# USBHume2.net
KiCad netlist of a schematic drawn in EAGLE
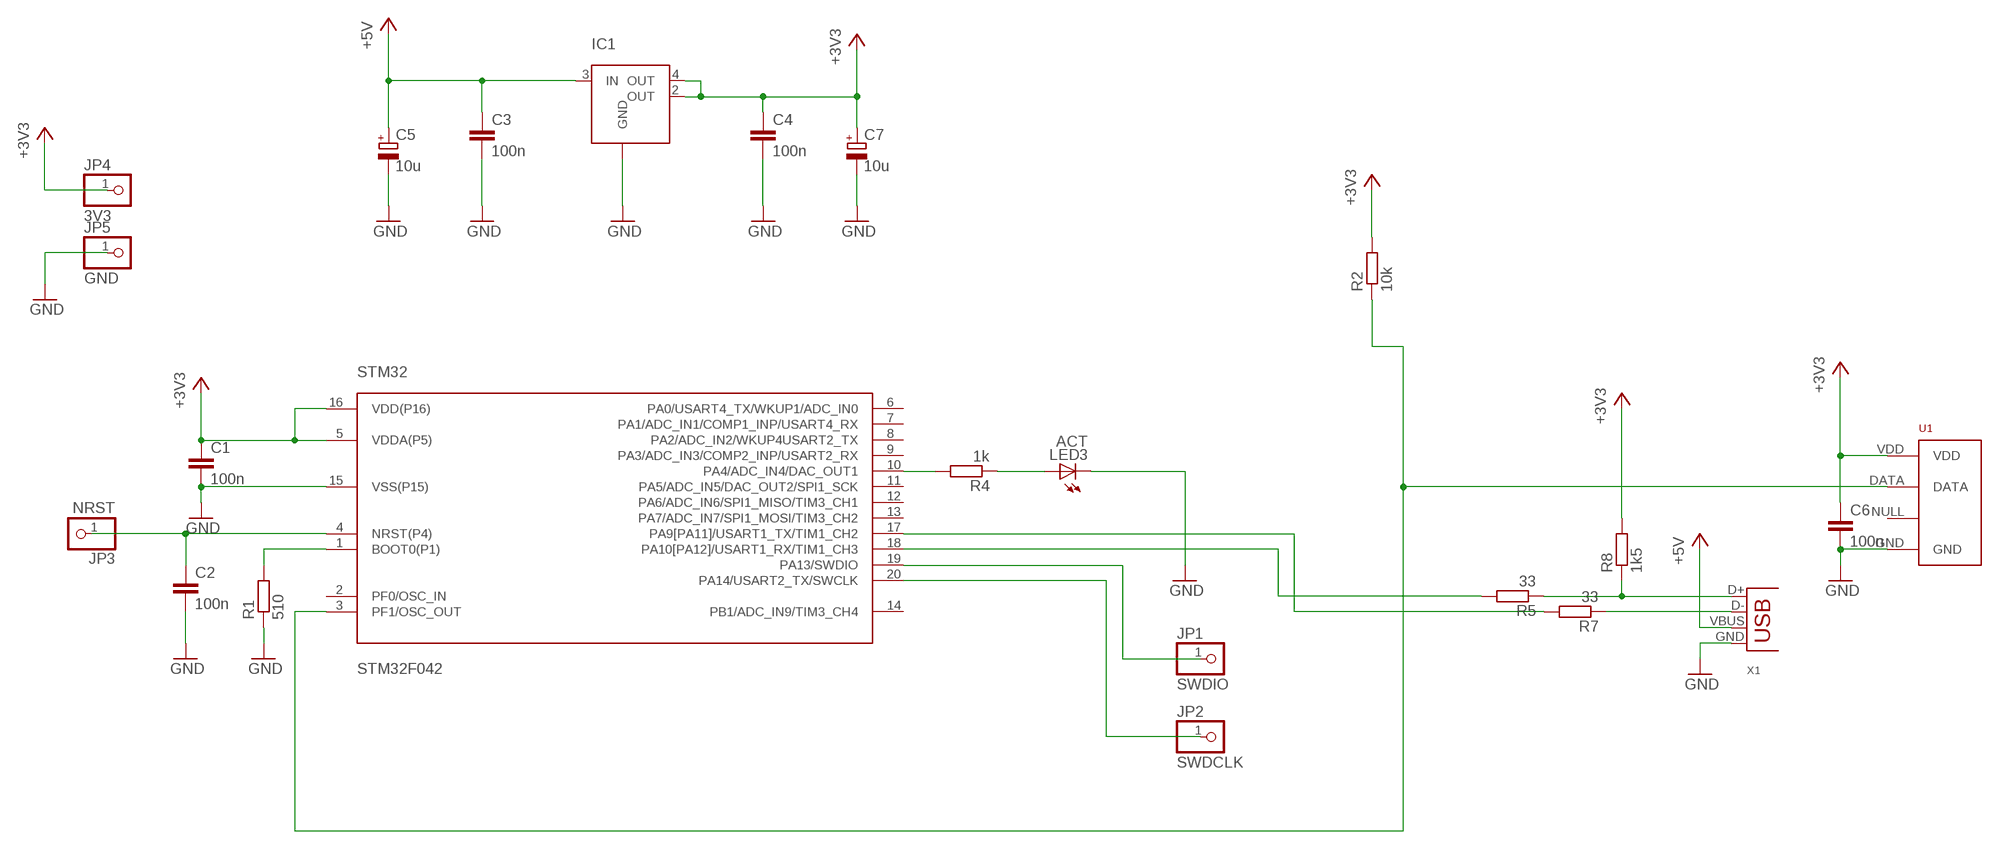
[diagram p0: schematic, sheet 1]

(export (version "E")
  (design (tool "Eeschema 10.0.6"))
  (components
    (comp (ref "C1")
      (value "100n")
      (footprint "eagle-import:C0805")
      (libsource (lib "eagle-import") (part "C-EUC0805"))
    )
    (comp (ref "C2")
      (value "100n")
      (footprint "eagle-import:C0805")
      (libsource (lib "eagle-import") (part "C-EUC0805"))
    )
    (comp (ref "C3")
      (value "100n")
      (footprint "eagle-import:C0805")
      (libsource (lib "eagle-import") (part "C-EUC0805"))
    )
    (comp (ref "C4")
      (value "100n")
      (footprint "eagle-import:C0805")
      (libsource (lib "eagle-import") (part "C-EUC0805"))
    )
    (comp (ref "C5")
      (value "10u")
      (footprint "eagle-import:A_3216-18W")
      (libsource (lib "eagle-import") (part "CPOL-EUA/3216-18W"))
    )
    (comp (ref "C6")
      (value "100n")
      (footprint "eagle-import:C0805")
      (libsource (lib "eagle-import") (part "C-EUC0805"))
    )
    (comp (ref "C7")
      (value "10u")
      (footprint "eagle-import:A_3216-18W")
      (libsource (lib "eagle-import") (part "CPOL-EUA/3216-18W"))
    )
    (comp (ref "IC1")
      (value "LM1117MP-3.3")
      (footprint "eagle-import:SOT223")
      (libsource (lib "eagle-import") (part "LM1117MP-3.3"))
    )
    (comp (ref "JP1")
      (value "SWDIO")
      (footprint "eagle-import:1X01")
      (libsource (lib "eagle-import") (part "PINHD-1X1"))
    )
    (comp (ref "JP2")
      (value "SWDCLK")
      (footprint "eagle-import:1X01")
      (libsource (lib "eagle-import") (part "PINHD-1X1"))
    )
    (comp (ref "JP3")
      (value "NRST")
      (footprint "eagle-import:1X01")
      (libsource (lib "eagle-import") (part "PINHD-1X1"))
    )
    (comp (ref "JP4")
      (value "3V3")
      (footprint "eagle-import:1X01")
      (libsource (lib "eagle-import") (part "PINHD-1X1"))
    )
    (comp (ref "JP5")
      (value "GND")
      (footprint "eagle-import:1X01")
      (libsource (lib "eagle-import") (part "PINHD-1X1"))
    )
    (comp (ref "LED3")
      (value "ACT")
      (footprint "eagle-import:CHIPLED_0805")
      (libsource (lib "eagle-import") (part "LEDCHIPLED_0805"))
    )
    (comp (ref "R1")
      (value "510")
      (footprint "eagle-import:M0805")
      (libsource (lib "eagle-import") (part "R-EU_M0805"))
    )
    (comp (ref "R2")
      (value "10k")
      (footprint "eagle-import:M0805")
      (libsource (lib "eagle-import") (part "R-EU_M0805"))
    )
    (comp (ref "R4")
      (value "1k")
      (footprint "eagle-import:M0805")
      (libsource (lib "eagle-import") (part "R-EU_M0805"))
    )
    (comp (ref "R5")
      (value "33")
      (footprint "eagle-import:M0805")
      (libsource (lib "eagle-import") (part "R-EU_M0805"))
    )
    (comp (ref "R7")
      (value "33")
      (footprint "eagle-import:M0805")
      (libsource (lib "eagle-import") (part "R-EU_M0805"))
    )
    (comp (ref "R8")
      (value "1k5")
      (footprint "eagle-import:M0805")
      (libsource (lib "eagle-import") (part "R-EU_M0805"))
    )
    (comp (ref "STM32")
      (value "STM32F042")
      (footprint "eagle-import:TSSOP20")
      (libsource (lib "eagle-import") (part "STM32F042"))
    )
    (comp (ref "U1")
      (value "RHT03_DHT-22_AM2302WIRED")
      (footprint "eagle-import:AM2302")
      (libsource (lib "eagle-import") (part "RHT03_DHT-22_AM2302WIRED"))
    )
    (comp (ref "X1")
      (value "USB-A-H")
      (footprint "eagle-import:USB-A-H")
      (libsource (lib "eagle-import") (part "USB-A-H"))
    )
  )
  (nets
    (net (code "1") (name "+3V3") (class "Default")
      (node (ref "C1") (pin "1") (pinfunction "1_1") (pintype "passive"))
      (node (ref "C4") (pin "1") (pinfunction "1_1") (pintype "passive"))
      (node (ref "C6") (pin "1") (pinfunction "1_1") (pintype "passive"))
      (node (ref "C7") (pin "+") (pinfunction "+_+") (pintype "passive"))
      (node (ref "IC1") (pin "2") (pinfunction "OUT_2") (pintype "power_in"))
      (node (ref "IC1") (pin "4") (pinfunction "OUT_4") (pintype "power_in"))
      (node (ref "JP4") (pin "1") (pinfunction "1_1") (pintype "passive"))
      (node (ref "R2") (pin "2") (pinfunction "2_2") (pintype "passive"))
      (node (ref "R8") (pin "2") (pinfunction "2_2") (pintype "passive"))
      (node (ref "STM32") (pin "16") (pinfunction "VDD(P16)_16") (pintype "bidirectional"))
      (node (ref "STM32") (pin "5") (pinfunction "VDDA(P5)_5") (pintype "bidirectional"))
      (node (ref "U1") (pin "VDD") (pinfunction "VDD_VDD") (pintype "power_in"))
    )
    (net (code "2") (name "+5V") (class "Default")
      (node (ref "C3") (pin "1") (pinfunction "1_1") (pintype "passive"))
      (node (ref "C5") (pin "+") (pinfunction "+_+") (pintype "passive"))
      (node (ref "IC1") (pin "3") (pinfunction "IN_3") (pintype "power_in"))
      (node (ref "X1") (pin "VBUS") (pinfunction "VBUS_VBUS") (pintype "bidirectional"))
    )
    (net (code "3") (name "GND") (class "Default")
      (node (ref "C1") (pin "2") (pinfunction "2_2") (pintype "passive"))
      (node (ref "C2") (pin "2") (pinfunction "2_2") (pintype "passive"))
      (node (ref "C3") (pin "2") (pinfunction "2_2") (pintype "passive"))
      (node (ref "C4") (pin "2") (pinfunction "2_2") (pintype "passive"))
      (node (ref "C5") (pin "-") (pinfunction "-_-") (pintype "passive"))
      (node (ref "C6") (pin "2") (pinfunction "2_2") (pintype "passive"))
      (node (ref "C7") (pin "-") (pinfunction "-_-") (pintype "passive"))
      (node (ref "IC1") (pin "1") (pinfunction "GND_1") (pintype "power_in"))
      (node (ref "JP5") (pin "1") (pinfunction "1_1") (pintype "passive"))
      (node (ref "LED3") (pin "C") (pinfunction "C_C") (pintype "passive"))
      (node (ref "R1") (pin "1") (pinfunction "1_1") (pintype "passive"))
      (node (ref "STM32") (pin "15") (pinfunction "VSS(P15)_15") (pintype "bidirectional"))
      (node (ref "U1") (pin "GND") (pinfunction "GND_GND") (pintype "power_in"))
      (node (ref "X1") (pin "GND") (pinfunction "GND_GND") (pintype "bidirectional"))
    )
    (net (code "4") (name "Net-(LED3-PadA)") (class "Default")
      (node (ref "LED3") (pin "A") (pinfunction "A_A") (pintype "passive"))
      (node (ref "R4") (pin "1") (pinfunction "1_1") (pintype "passive"))
    )
    (net (code "5") (name "Net-(R5-Pad1)") (class "Default")
      (node (ref "R5") (pin "1") (pinfunction "1_1") (pintype "passive"))
      (node (ref "R8") (pin "1") (pinfunction "1_1") (pintype "passive"))
      (node (ref "X1") (pin "D+") (pinfunction "D+_D+") (pintype "bidirectional"))
    )
    (net (code "6") (name "Net-(R7-Pad1)") (class "Default")
      (node (ref "R7") (pin "1") (pinfunction "1_1") (pintype "passive"))
      (node (ref "X1") (pin "D-") (pinfunction "D-_D-") (pintype "bidirectional"))
    )
    (net (code "7") (name "Net-(STM32-BOOT0(P1))") (class "Default")
      (node (ref "R1") (pin "2") (pinfunction "2_2") (pintype "passive"))
      (node (ref "STM32") (pin "1") (pinfunction "BOOT0(P1)_1") (pintype "bidirectional"))
    )
    (net (code "8") (name "Net-(STM32-NRST(P4))") (class "Default")
      (node (ref "C2") (pin "1") (pinfunction "1_1") (pintype "passive"))
      (node (ref "JP3") (pin "1") (pinfunction "1_1") (pintype "passive"))
      (node (ref "STM32") (pin "4") (pinfunction "NRST(P4)_4") (pintype "bidirectional"))
    )
    (net (code "9") (name "Net-(STM32-PA4{slash}ADC_IN4{slash}DAC_OUT1)") (class "Default")
      (node (ref "R4") (pin "2") (pinfunction "2_2") (pintype "passive"))
      (node (ref "STM32") (pin "10") (pinfunction "PA4/ADC_IN4/DAC_OUT1_10") (pintype "bidirectional"))
    )
    (net (code "10") (name "Net-(STM32-PA9[PA11]{slash}USART1_TX{slash}TIM1_CH2)") (class "Default")
      (node (ref "R7") (pin "2") (pinfunction "2_2") (pintype "passive"))
      (node (ref "STM32") (pin "17") (pinfunction "PA9[PA11]/USART1_TX/TIM1_CH2_17") (pintype "bidirectional"))
    )
    (net (code "11") (name "Net-(STM32-PA10[PA12]{slash}USART1_RX{slash}TIM1_CH3)") (class "Default")
      (node (ref "R5") (pin "2") (pinfunction "2_2") (pintype "passive"))
      (node (ref "STM32") (pin "18") (pinfunction "PA10[PA12]/USART1_RX/TIM1_CH3_18") (pintype "bidirectional"))
    )
    (net (code "12") (name "Net-(STM32-PA13{slash}SWDIO)") (class "Default")
      (node (ref "JP1") (pin "1") (pinfunction "1_1") (pintype "passive"))
      (node (ref "STM32") (pin "19") (pinfunction "PA13/SWDIO_19") (pintype "bidirectional"))
    )
    (net (code "13") (name "Net-(STM32-PA14{slash}USART2_TX{slash}SWCLK)") (class "Default")
      (node (ref "JP2") (pin "1") (pinfunction "1_1") (pintype "passive"))
      (node (ref "STM32") (pin "20") (pinfunction "PA14/USART2_TX/SWCLK_20") (pintype "bidirectional"))
    )
    (net (code "14") (name "Net-(STM32-PF1{slash}OSC_OUT)") (class "Default")
      (node (ref "R2") (pin "1") (pinfunction "1_1") (pintype "passive"))
      (node (ref "STM32") (pin "3") (pinfunction "PF1/OSC_OUT_3") (pintype "bidirectional"))
      (node (ref "U1") (pin "DATA") (pinfunction "DATA_DATA") (pintype "bidirectional"))
    )
    (net (code "15") (name "unconnected-(STM32-PA0{slash}USART4_TX{slash}WKUP1{slash}ADC_IN0-Pad6)") (class "Default")
      (node (ref "STM32") (pin "6") (pinfunction "PA0/USART4_TX/WKUP1/ADC_IN0_6") (pintype "bidirectional"))
    )
    (net (code "16") (name "unconnected-(STM32-PA1{slash}ADC_IN1{slash}COMP1_INP{slash}USART4_RX-Pad7)") (class "Default")
      (node (ref "STM32") (pin "7") (pinfunction "PA1/ADC_IN1/COMP1_INP/USART4_RX_7") (pintype "bidirectional"))
    )
    (net (code "17") (name "unconnected-(STM32-PA2{slash}ADC_IN2{slash}WKUP4USART2_TX-Pad8)") (class "Default")
      (node (ref "STM32") (pin "8") (pinfunction "PA2/ADC_IN2/WKUP4USART2_TX_8") (pintype "bidirectional"))
    )
    (net (code "18") (name "unconnected-(STM32-PA3{slash}ADC_IN3{slash}COMP2_INP{slash}USART2_RX-Pad9)") (class "Default")
      (node (ref "STM32") (pin "9") (pinfunction "PA3/ADC_IN3/COMP2_INP/USART2_RX_9") (pintype "bidirectional"))
    )
    (net (code "19") (name "unconnected-(STM32-PA5{slash}ADC_IN5{slash}DAC_OUT2{slash}SPI1_SCK-Pad11)") (class "Default")
      (node (ref "STM32") (pin "11") (pinfunction "PA5/ADC_IN5/DAC_OUT2/SPI1_SCK_11") (pintype "bidirectional"))
    )
    (net (code "20") (name "unconnected-(STM32-PA6{slash}ADC_IN6{slash}SPI1_MISO{slash}TIM3_CH1-Pad12)") (class "Default")
      (node (ref "STM32") (pin "12") (pinfunction "PA6/ADC_IN6/SPI1_MISO/TIM3_CH1_12") (pintype "bidirectional"))
    )
    (net (code "21") (name "unconnected-(STM32-PA7{slash}ADC_IN7{slash}SPI1_MOSI{slash}TIM3_CH2-Pad13)") (class "Default")
      (node (ref "STM32") (pin "13") (pinfunction "PA7/ADC_IN7/SPI1_MOSI/TIM3_CH2_13") (pintype "bidirectional"))
    )
    (net (code "22") (name "unconnected-(STM32-PB1{slash}ADC_IN9{slash}TIM3_CH4-Pad14)") (class "Default")
      (node (ref "STM32") (pin "14") (pinfunction "PB1/ADC_IN9/TIM3_CH4_14") (pintype "bidirectional"))
    )
    (net (code "23") (name "unconnected-(STM32-PF0{slash}OSC_IN-Pad2)") (class "Default")
      (node (ref "STM32") (pin "2") (pinfunction "PF0/OSC_IN_2") (pintype "bidirectional"))
    )
    (net (code "24") (name "unconnected-(U1-PadNULL)") (class "Default")
      (node (ref "U1") (pin "NULL") (pinfunction "NULL_NULL") (pintype "no_connect"))
    )
  )
)
